# qmc5883l.net
KiCad netlist of a schematic drawn in Altium Designer
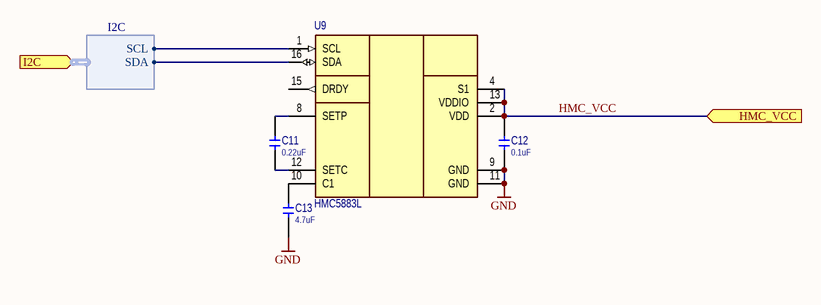
[diagram p0: qmc5883l.SchDoc]

(export (version "E")
  (design (tool "Eeschema 10.0.6"))
  (components
    (comp (ref "C11")
      (value "0.22uF")
      (footprint "CERCAP 0402")
      (description "Capacitor")
      (fields (field (name "Comment") "CERCAP 0402 0.22uF * X7R"))
      (libsource (lib "!main") (part "!Capacitor"))
    )
    (comp (ref "C12")
      (value "0.1uF")
      (footprint "CERCAP 0402")
      (description "Capacitor")
      (fields (field (name "Comment") "CERCAP 0402 0.1uF * X7R"))
      (libsource (lib "!main") (part "!Capacitor"))
    )
    (comp (ref "C13")
      (value "4.7uF")
      (footprint "CERCAP 0603")
      (description "Capacitor")
      (fields (field (name "Comment") "CERCAP 0603 4.7uF * X7R"))
      (libsource (lib "!main") (part "!Capacitor"))
    )
    (comp (ref "U9")
      (value "HMC5883L")
      (footprint "LGA16_HMC5883L")
      (description "Gyro")
      (libsource (lib "sensors") (part "Q/HMC5883l"))
    )
  )
  (nets
    (net (code "2") (name "/HMC_VCC") (class "Default")
      (node (ref "C12") (pin "2") (pintype "passive"))
      (node (ref "U9") (pin "13") (pinfunction "VDDIO_13") (pintype "power_in"))
      (node (ref "U9") (pin "2") (pinfunction "VDD_2") (pintype "power_in"))
      (node (ref "U9") (pin "4") (pinfunction "S1_4") (pintype "passive"))
    )
    (net (code "3") (name "/SCL") (class "Default")
      (node (ref "U9") (pin "1") (pinfunction "SCL_1") (pintype "input"))
    )
    (net (code "4") (name "/SDA") (class "Default")
      (node (ref "U9") (pin "16") (pinfunction "SDA_16") (pintype "bidirectional"))
    )
    (net (code "6") (name "GND") (class "Default")
      (node (ref "C12") (pin "1") (pintype "passive"))
      (node (ref "C13") (pin "1") (pintype "passive"))
      (node (ref "U9") (pin "11") (pinfunction "GND_11") (pintype "power_in"))
      (node (ref "U9") (pin "9") (pinfunction "GND_9") (pintype "power_in"))
    )
    (net (code "7") (name "Net-(U9-C1)") (class "Default")
      (node (ref "C13") (pin "2") (pintype "passive"))
      (node (ref "U9") (pin "10") (pinfunction "C1_10") (pintype "power_in"))
    )
    (net (code "8") (name "Net-(U9-SETC)") (class "Default")
      (node (ref "C11") (pin "1") (pintype "passive"))
      (node (ref "U9") (pin "12") (pinfunction "SETC_12") (pintype "power_in"))
    )
    (net (code "9") (name "Net-(U9-SETP)") (class "Default")
      (node (ref "C11") (pin "2") (pintype "passive"))
      (node (ref "U9") (pin "8") (pinfunction "SETP_8") (pintype "power_in"))
    )
    (net (code "10") (name "unconnected-(U9-DRDY-Pad15)") (class "Default")
      (node (ref "U9") (pin "15") (pinfunction "DRDY_15") (pintype "output"))
    )
  )
)
